# esquema.net
KiCad netlist of a schematic drawn in EAGLE
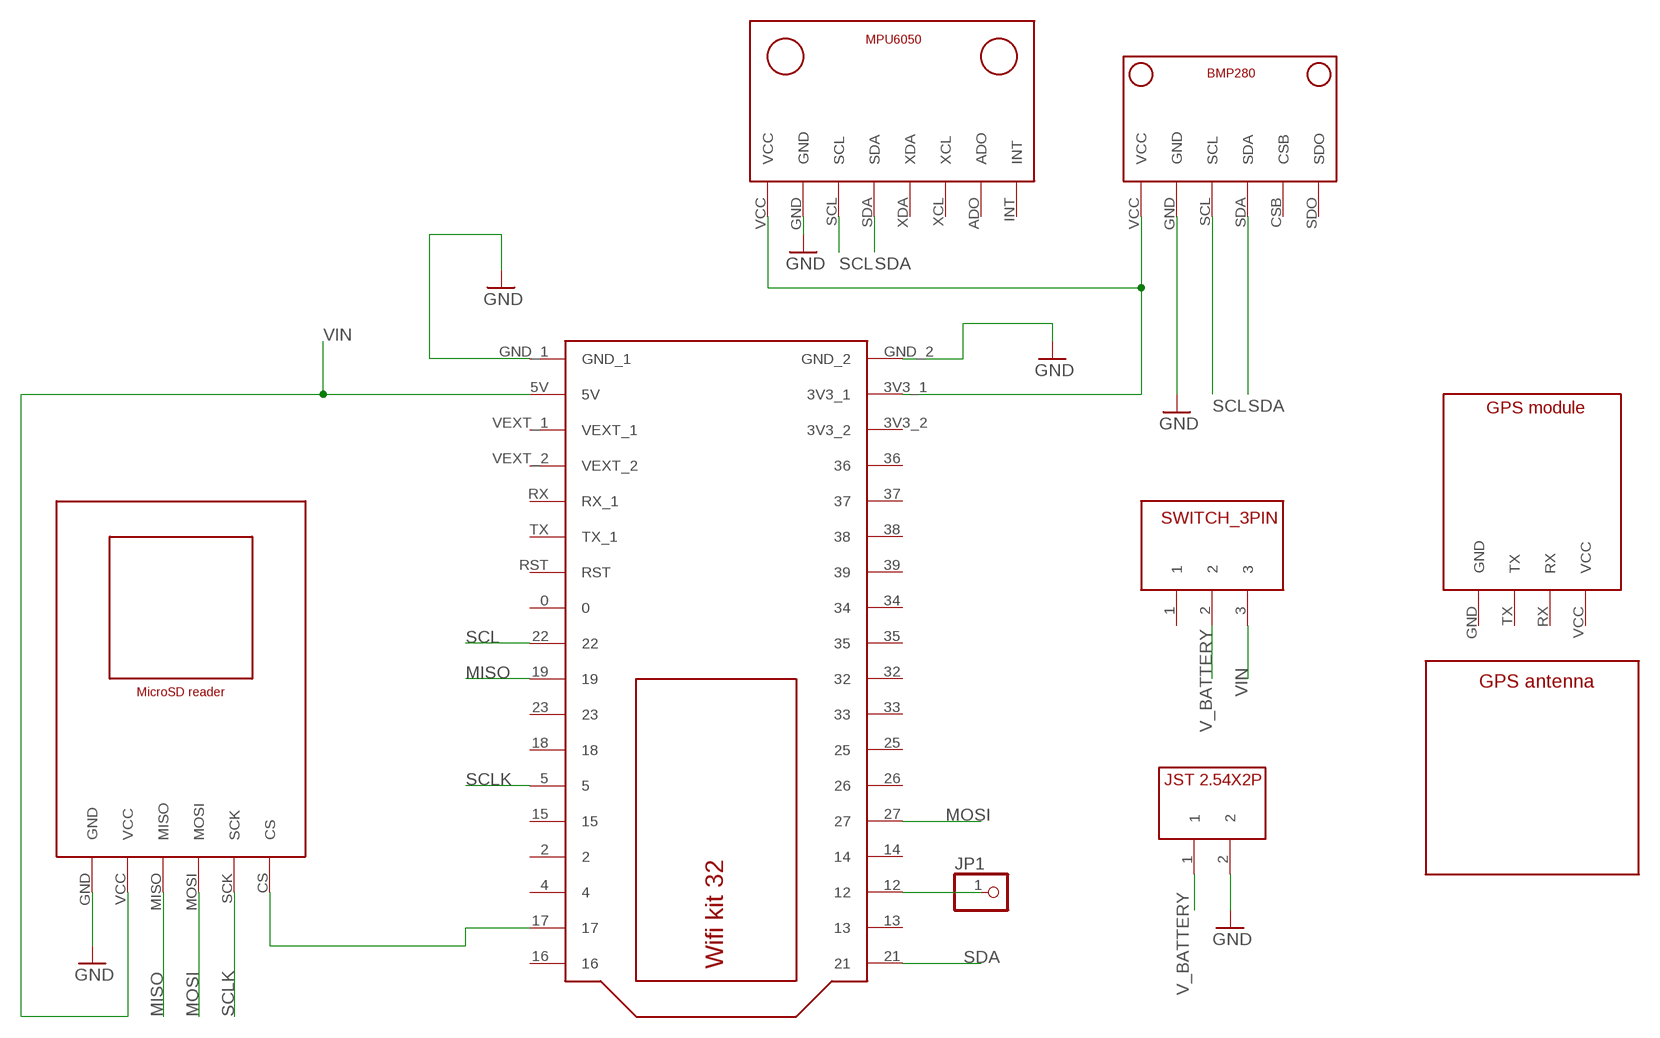
[diagram p0: schematic, sheet 1]

(export (version "E")
  (design (tool "Eeschema 10.0.6"))
  (components
    (comp (ref "JP1")
      (value "PINHD-1X1")
      (footprint "eagle-import:1X01")
      (libsource (lib "eagle-import") (part "PINHD-1X1"))
    )
    (comp (ref "U$1")
      (value "BMP280V1")
      (footprint "eagle-import:BMP280_FOOTPRINT")
      (libsource (lib "eagle-import") (part "BMP280V1"))
    )
    (comp (ref "U$2")
      (value "MICROSD_READER")
      (footprint "eagle-import:MICROSD_READER_FOOTPRINT")
      (libsource (lib "eagle-import") (part "MICROSD_READER"))
    )
    (comp (ref "U$3")
      (value "MPU6050V1")
      (footprint "eagle-import:MPU6050_FOOTPRINT")
      (libsource (lib "eagle-import") (part "MPU6050V1"))
    )
    (comp (ref "U$4")
      (value "WIFI_KIT32")
      (footprint "eagle-import:WIFI_KIT32")
      (libsource (lib "eagle-import") (part "WIFI_KIT32"))
    )
    (comp (ref "U$5")
      (value "JST2.54X2P")
      (footprint "eagle-import:JST2.54X2P_FOOTPRINT")
      (libsource (lib "eagle-import") (part "JST2.54X2P"))
    )
    (comp (ref "U$6")
      (value "SWITCH_3PIN")
      (footprint "eagle-import:SWITCH_3PIN")
      (libsource (lib "eagle-import") (part "SWITCH_3PIN"))
    )
    (comp (ref "U$7")
      (value "GPS_MODULE")
      (footprint "eagle-import:GPS_MODULE_FOOTPRINT")
      (libsource (lib "eagle-import") (part "GPS_MODULE"))
    )
    (comp (ref "U$8")
      (value "GPS_ANTENNA")
      (footprint "eagle-import:GPS_ANTENNA_FOOTPRINT")
      (libsource (lib "eagle-import") (part "GPS_ANTENNA"))
    )
  )
  (nets
    (net (code "1") (name "/MISO") (class "Default")
      (node (ref "U$2") (pin "MISO") (pinfunction "MISO_MISO") (pintype "bidirectional"))
      (node (ref "U$4") (pin "19") (pinfunction "19_19") (pintype "bidirectional"))
    )
    (net (code "2") (name "/MOSI") (class "Default")
      (node (ref "U$2") (pin "MOSI") (pinfunction "MOSI_MOSI") (pintype "bidirectional"))
      (node (ref "U$4") (pin "27") (pinfunction "27_27") (pintype "bidirectional"))
    )
    (net (code "3") (name "/SCL") (class "Default")
      (node (ref "U$1") (pin "SCL") (pinfunction "SCL_SCL") (pintype "bidirectional"))
      (node (ref "U$3") (pin "SCL") (pinfunction "SCL_SCL") (pintype "bidirectional"))
      (node (ref "U$4") (pin "22") (pinfunction "22_22") (pintype "bidirectional"))
    )
    (net (code "4") (name "/SCLK") (class "Default")
      (node (ref "U$2") (pin "SCK") (pinfunction "SCK_SCK") (pintype "bidirectional"))
      (node (ref "U$4") (pin "5") (pinfunction "5_5") (pintype "bidirectional"))
    )
    (net (code "5") (name "/SDA") (class "Default")
      (node (ref "U$1") (pin "SDA") (pinfunction "SDA_SDA") (pintype "bidirectional"))
      (node (ref "U$3") (pin "SDA") (pinfunction "SDA_SDA") (pintype "bidirectional"))
      (node (ref "U$4") (pin "21") (pinfunction "21_21") (pintype "bidirectional"))
    )
    (net (code "6") (name "/VIN") (class "Default")
      (node (ref "U$2") (pin "VCC") (pinfunction "VCC_VCC") (pintype "bidirectional"))
      (node (ref "U$4") (pin "5V") (pinfunction "5V_5V") (pintype "bidirectional"))
      (node (ref "U$6") (pin "3") (pinfunction "3_3") (pintype "bidirectional"))
    )
    (net (code "7") (name "/V_BATTERY") (class "Default")
      (node (ref "U$5") (pin "1") (pinfunction "1_1") (pintype "bidirectional"))
      (node (ref "U$6") (pin "2") (pinfunction "2_2") (pintype "bidirectional"))
    )
    (net (code "8") (name "GND") (class "Default")
      (node (ref "U$1") (pin "GND") (pinfunction "GND_GND") (pintype "bidirectional"))
      (node (ref "U$2") (pin "GND") (pinfunction "GND_GND") (pintype "bidirectional"))
      (node (ref "U$3") (pin "GND") (pinfunction "GND_GND") (pintype "bidirectional"))
      (node (ref "U$4") (pin "GND_1") (pinfunction "GND_1_GND_1") (pintype "bidirectional"))
      (node (ref "U$4") (pin "GND_2") (pinfunction "GND_2_GND_2") (pintype "bidirectional"))
      (node (ref "U$5") (pin "2") (pinfunction "2_2") (pintype "bidirectional"))
    )
    (net (code "9") (name "Net-(JP1-Pad1)") (class "Default")
      (node (ref "JP1") (pin "1") (pinfunction "1_1") (pintype "passive"))
      (node (ref "U$4") (pin "12") (pinfunction "12_12") (pintype "bidirectional"))
    )
    (net (code "10") (name "Net-(U$1-PadVCC)") (class "Default")
      (node (ref "U$1") (pin "VCC") (pinfunction "VCC_VCC") (pintype "bidirectional"))
      (node (ref "U$3") (pin "VCC") (pinfunction "VCC_VCC") (pintype "bidirectional"))
      (node (ref "U$4") (pin "3V3_1") (pinfunction "3V3_1_3V3_1") (pintype "bidirectional"))
    )
    (net (code "11") (name "Net-(U$2-PadCS)") (class "Default")
      (node (ref "U$2") (pin "CS") (pinfunction "CS_CS") (pintype "bidirectional"))
      (node (ref "U$4") (pin "17") (pinfunction "17_17") (pintype "bidirectional"))
    )
    (net (code "12") (name "unconnected-(U$1-PadCSB)") (class "Default")
      (node (ref "U$1") (pin "CSB") (pinfunction "CSB_CSB") (pintype "bidirectional"))
    )
    (net (code "13") (name "unconnected-(U$1-PadSDO)") (class "Default")
      (node (ref "U$1") (pin "SDO") (pinfunction "SDO_SDO") (pintype "bidirectional"))
    )
    (net (code "14") (name "unconnected-(U$3-PadADO)") (class "Default")
      (node (ref "U$3") (pin "ADO") (pinfunction "ADO_ADO") (pintype "bidirectional"))
    )
    (net (code "15") (name "unconnected-(U$3-PadINT)") (class "Default")
      (node (ref "U$3") (pin "INT") (pinfunction "INT_INT") (pintype "bidirectional"))
    )
    (net (code "16") (name "unconnected-(U$3-PadXCL)") (class "Default")
      (node (ref "U$3") (pin "XCL") (pinfunction "XCL_XCL") (pintype "bidirectional"))
    )
    (net (code "17") (name "unconnected-(U$3-PadXDA)") (class "Default")
      (node (ref "U$3") (pin "XDA") (pinfunction "XDA_XDA") (pintype "bidirectional"))
    )
    (net (code "18") (name "unconnected-(U$4-Pad0)") (class "Default")
      (node (ref "U$4") (pin "0") (pinfunction "0_0") (pintype "bidirectional"))
    )
    (net (code "19") (name "unconnected-(U$4-Pad2)") (class "Default")
      (node (ref "U$4") (pin "2") (pinfunction "2_2") (pintype "bidirectional"))
    )
    (net (code "20") (name "unconnected-(U$4-Pad3V3_2)") (class "Default")
      (node (ref "U$4") (pin "3V3_2") (pinfunction "3V3_2_3V3_2") (pintype "bidirectional"))
    )
    (net (code "21") (name "unconnected-(U$4-Pad4)") (class "Default")
      (node (ref "U$4") (pin "4") (pinfunction "4_4") (pintype "bidirectional"))
    )
    (net (code "22") (name "unconnected-(U$4-Pad13)") (class "Default")
      (node (ref "U$4") (pin "13") (pinfunction "13_13") (pintype "bidirectional"))
    )
    (net (code "23") (name "unconnected-(U$4-Pad14)") (class "Default")
      (node (ref "U$4") (pin "14") (pinfunction "14_14") (pintype "bidirectional"))
    )
    (net (code "24") (name "unconnected-(U$4-Pad15)") (class "Default")
      (node (ref "U$4") (pin "15") (pinfunction "15_15") (pintype "bidirectional"))
    )
    (net (code "25") (name "unconnected-(U$4-Pad16)") (class "Default")
      (node (ref "U$4") (pin "16") (pinfunction "16_16") (pintype "bidirectional"))
    )
    (net (code "26") (name "unconnected-(U$4-Pad18)") (class "Default")
      (node (ref "U$4") (pin "18") (pinfunction "18_18") (pintype "bidirectional"))
    )
    (net (code "27") (name "unconnected-(U$4-Pad23)") (class "Default")
      (node (ref "U$4") (pin "23") (pinfunction "23_23") (pintype "bidirectional"))
    )
    (net (code "28") (name "unconnected-(U$4-Pad25)") (class "Default")
      (node (ref "U$4") (pin "25") (pinfunction "25_25") (pintype "bidirectional"))
    )
    (net (code "29") (name "unconnected-(U$4-Pad26)") (class "Default")
      (node (ref "U$4") (pin "26") (pinfunction "26_26") (pintype "bidirectional"))
    )
    (net (code "30") (name "unconnected-(U$4-Pad32)") (class "Default")
      (node (ref "U$4") (pin "32") (pinfunction "32_32") (pintype "bidirectional"))
    )
    (net (code "31") (name "unconnected-(U$4-Pad33)") (class "Default")
      (node (ref "U$4") (pin "33") (pinfunction "33_33") (pintype "bidirectional"))
    )
    (net (code "32") (name "unconnected-(U$4-Pad34)") (class "Default")
      (node (ref "U$4") (pin "34") (pinfunction "34_34") (pintype "bidirectional"))
    )
    (net (code "33") (name "unconnected-(U$4-Pad35)") (class "Default")
      (node (ref "U$4") (pin "35") (pinfunction "35_35") (pintype "bidirectional"))
    )
    (net (code "34") (name "unconnected-(U$4-Pad36)") (class "Default")
      (node (ref "U$4") (pin "36") (pinfunction "36_36") (pintype "bidirectional"))
    )
    (net (code "35") (name "unconnected-(U$4-Pad37)") (class "Default")
      (node (ref "U$4") (pin "37") (pinfunction "37_37") (pintype "bidirectional"))
    )
    (net (code "36") (name "unconnected-(U$4-Pad38)") (class "Default")
      (node (ref "U$4") (pin "38") (pinfunction "38_38") (pintype "bidirectional"))
    )
    (net (code "37") (name "unconnected-(U$4-Pad39)") (class "Default")
      (node (ref "U$4") (pin "39") (pinfunction "39_39") (pintype "bidirectional"))
    )
    (net (code "38") (name "unconnected-(U$4-PadRST)") (class "Default")
      (node (ref "U$4") (pin "RST") (pinfunction "RST_RST") (pintype "bidirectional"))
    )
    (net (code "39") (name "unconnected-(U$4-PadVEXT_1)") (class "Default")
      (node (ref "U$4") (pin "VEXT_1") (pinfunction "VEXT_1_VEXT_1") (pintype "bidirectional"))
    )
    (net (code "40") (name "unconnected-(U$4-PadVEXT_2)") (class "Default")
      (node (ref "U$4") (pin "VEXT_2") (pinfunction "VEXT_2_VEXT_2") (pintype "bidirectional"))
    )
    (net (code "41") (name "unconnected-(U$4-RX_1-PadRX)") (class "Default")
      (node (ref "U$4") (pin "RX") (pinfunction "RX_1_RX") (pintype "bidirectional"))
    )
    (net (code "42") (name "unconnected-(U$4-TX_1-PadTX)") (class "Default")
      (node (ref "U$4") (pin "TX") (pinfunction "TX_1_TX") (pintype "bidirectional"))
    )
    (net (code "43") (name "unconnected-(U$6-Pad1)") (class "Default")
      (node (ref "U$6") (pin "1") (pinfunction "1_1") (pintype "bidirectional"))
    )
    (net (code "44") (name "unconnected-(U$7-PadGND)") (class "Default")
      (node (ref "U$7") (pin "GND") (pinfunction "GND_GND") (pintype "bidirectional"))
    )
    (net (code "45") (name "unconnected-(U$7-PadRX)") (class "Default")
      (node (ref "U$7") (pin "RX") (pinfunction "RX_RX") (pintype "bidirectional"))
    )
    (net (code "46") (name "unconnected-(U$7-PadTX)") (class "Default")
      (node (ref "U$7") (pin "TX") (pinfunction "TX_TX") (pintype "bidirectional"))
    )
    (net (code "47") (name "unconnected-(U$7-PadVCC)") (class "Default")
      (node (ref "U$7") (pin "VCC") (pinfunction "VCC_VCC") (pintype "bidirectional"))
    )
  )
)
